# io-ol.net
KiCad netlist of a schematic drawn in EAGLE
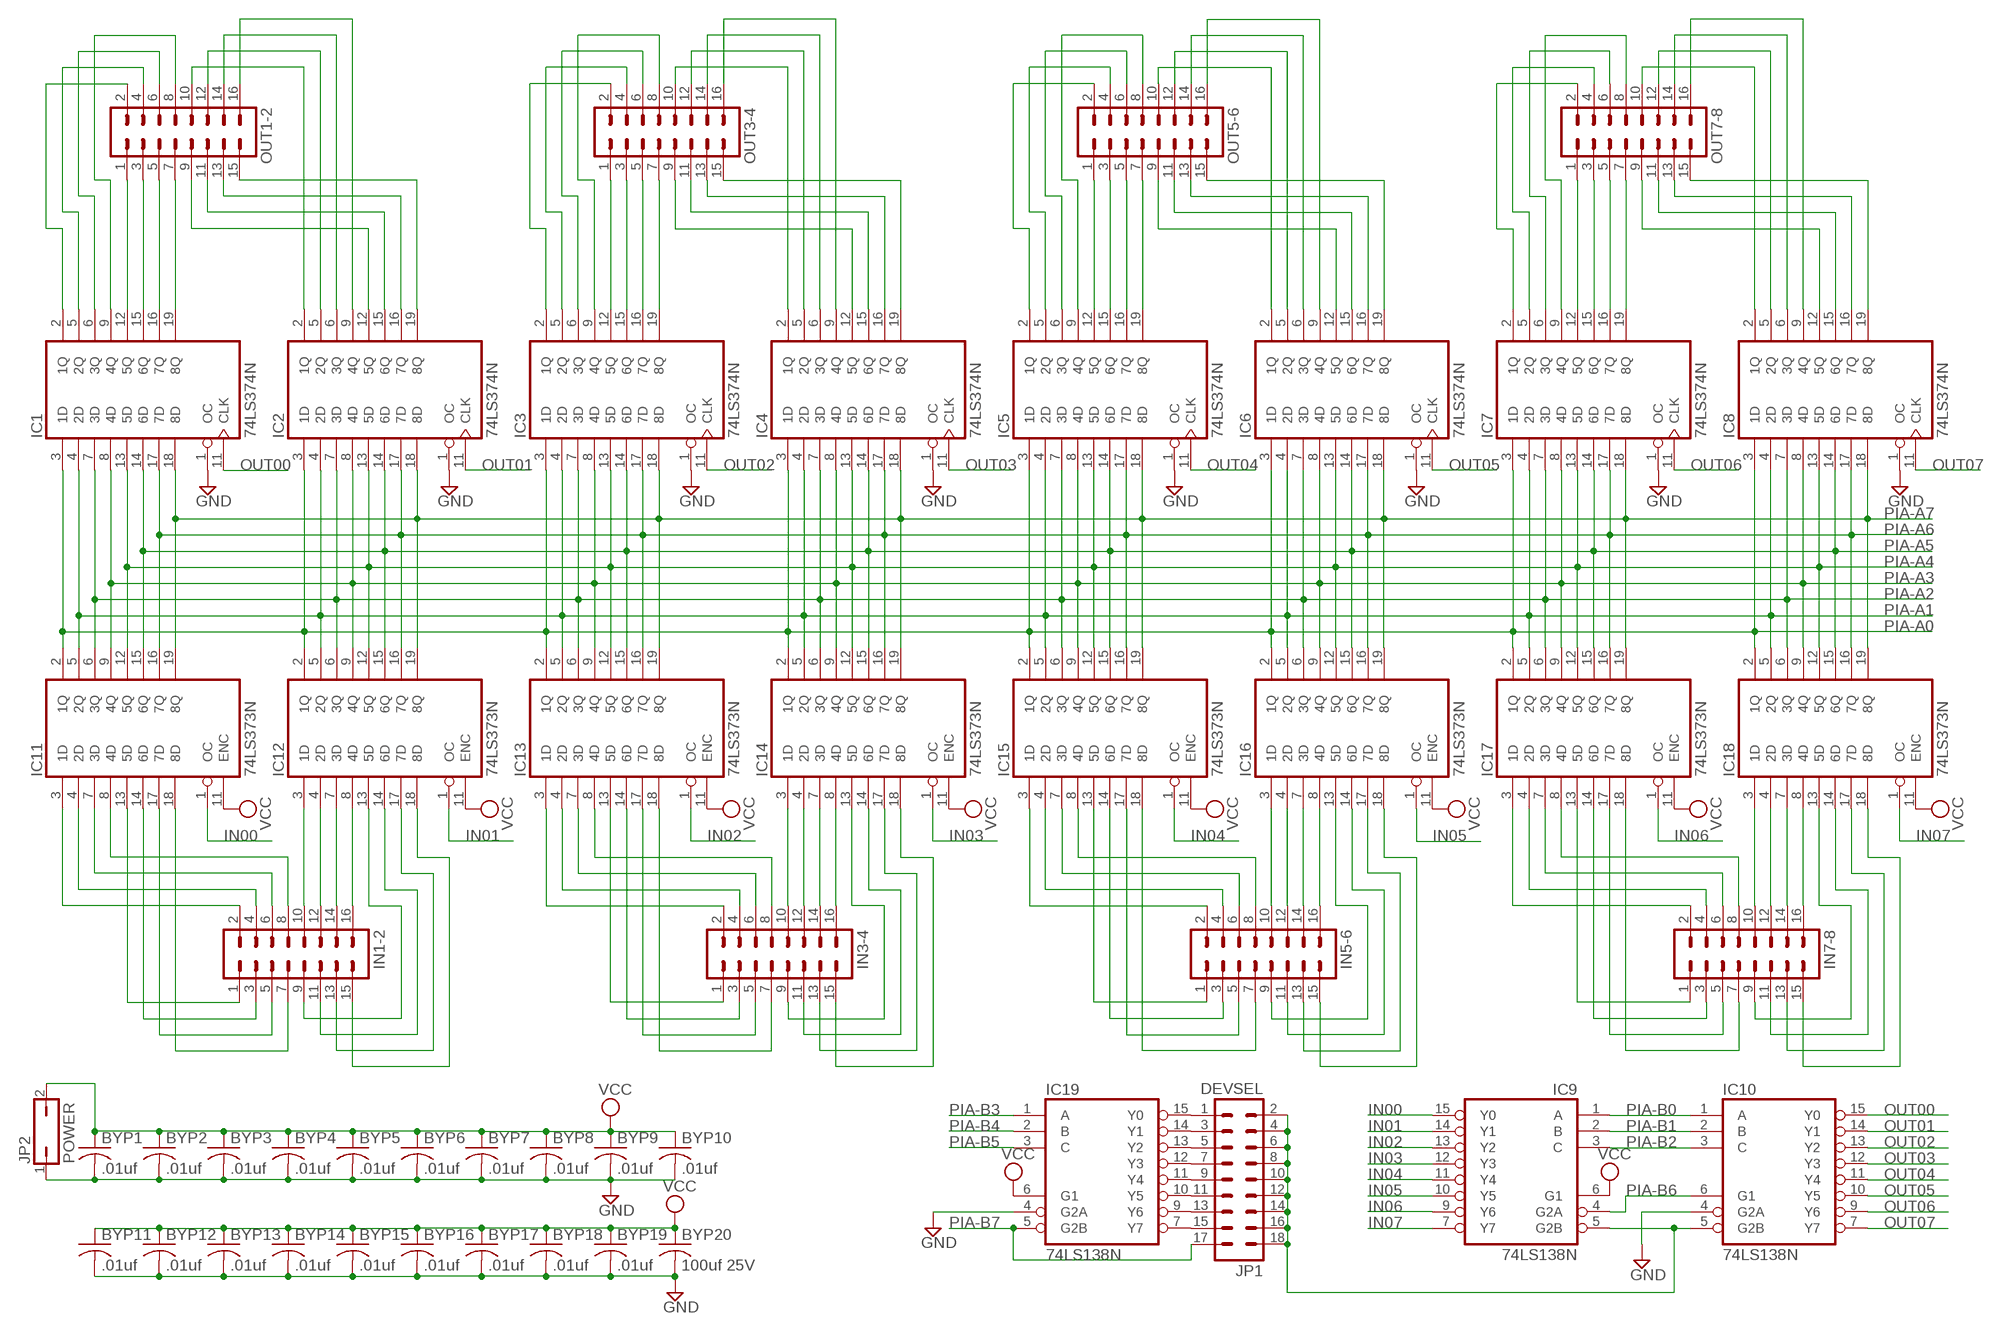
[diagram p0: schematic, sheet 1]
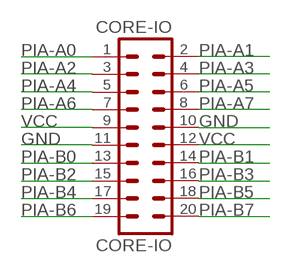
[diagram p1: schematic, sheet 2]

(export (version "E")
  (design (tool "Eeschema 10.0.6"))
  (components
    (comp (ref "BYP1")
      (value ".01uf")
      (footprint "eagle-import:C050-025X075")
      (libsource (lib "eagle-import") (part "C-US050-025X075"))
    )
    (comp (ref "BYP2")
      (value ".01uf")
      (footprint "eagle-import:C050-025X075")
      (libsource (lib "eagle-import") (part "C-US050-025X075"))
    )
    (comp (ref "BYP3")
      (value ".01uf")
      (footprint "eagle-import:C050-025X075")
      (libsource (lib "eagle-import") (part "C-US050-025X075"))
    )
    (comp (ref "BYP4")
      (value ".01uf")
      (footprint "eagle-import:C050-025X075")
      (libsource (lib "eagle-import") (part "C-US050-025X075"))
    )
    (comp (ref "BYP5")
      (value ".01uf")
      (footprint "eagle-import:C050-025X075")
      (libsource (lib "eagle-import") (part "C-US050-025X075"))
    )
    (comp (ref "BYP6")
      (value ".01uf")
      (footprint "eagle-import:C050-025X075")
      (libsource (lib "eagle-import") (part "C-US050-025X075"))
    )
    (comp (ref "BYP7")
      (value ".01uf")
      (footprint "eagle-import:C050-025X075")
      (libsource (lib "eagle-import") (part "C-US050-025X075"))
    )
    (comp (ref "BYP8")
      (value ".01uf")
      (footprint "eagle-import:C050-025X075")
      (libsource (lib "eagle-import") (part "C-US050-025X075"))
    )
    (comp (ref "BYP9")
      (value ".01uf")
      (footprint "eagle-import:C050-025X075")
      (libsource (lib "eagle-import") (part "C-US050-025X075"))
    )
    (comp (ref "BYP10")
      (value ".01uf")
      (footprint "eagle-import:C050-025X075")
      (libsource (lib "eagle-import") (part "C-US050-025X075"))
    )
    (comp (ref "BYP11")
      (value ".01uf")
      (footprint "eagle-import:C050-025X075")
      (libsource (lib "eagle-import") (part "C-US050-025X075"))
    )
    (comp (ref "BYP12")
      (value ".01uf")
      (footprint "eagle-import:C050-025X075")
      (libsource (lib "eagle-import") (part "C-US050-025X075"))
    )
    (comp (ref "BYP13")
      (value ".01uf")
      (footprint "eagle-import:C050-025X075")
      (libsource (lib "eagle-import") (part "C-US050-025X075"))
    )
    (comp (ref "BYP14")
      (value ".01uf")
      (footprint "eagle-import:C050-025X075")
      (libsource (lib "eagle-import") (part "C-US050-025X075"))
    )
    (comp (ref "BYP15")
      (value ".01uf")
      (footprint "eagle-import:C050-025X075")
      (libsource (lib "eagle-import") (part "C-US050-025X075"))
    )
    (comp (ref "BYP16")
      (value ".01uf")
      (footprint "eagle-import:C050-025X075")
      (libsource (lib "eagle-import") (part "C-US050-025X075"))
    )
    (comp (ref "BYP17")
      (value ".01uf")
      (footprint "eagle-import:C050-025X075")
      (libsource (lib "eagle-import") (part "C-US050-025X075"))
    )
    (comp (ref "BYP18")
      (value ".01uf")
      (footprint "eagle-import:C050-025X075")
      (libsource (lib "eagle-import") (part "C-US050-025X075"))
    )
    (comp (ref "BYP19")
      (value ".01uf")
      (footprint "eagle-import:C050-025X075")
      (libsource (lib "eagle-import") (part "C-US050-025X075"))
    )
    (comp (ref "BYP20")
      (value "100uf 25V")
      (footprint "eagle-import:C150-064X183")
      (libsource (lib "eagle-import") (part "C-US150-064X183"))
    )
    (comp (ref "IC1")
      (value "74LS374N")
      (footprint "eagle-import:DIL20")
      (libsource (lib "eagle-import") (part "74374NLS"))
    )
    (comp (ref "IC2")
      (value "74LS374N")
      (footprint "eagle-import:DIL20")
      (libsource (lib "eagle-import") (part "74374NLS"))
    )
    (comp (ref "IC3")
      (value "74LS374N")
      (footprint "eagle-import:DIL20")
      (libsource (lib "eagle-import") (part "74374NLS"))
    )
    (comp (ref "IC4")
      (value "74LS374N")
      (footprint "eagle-import:DIL20")
      (libsource (lib "eagle-import") (part "74374NLS"))
    )
    (comp (ref "IC5")
      (value "74LS374N")
      (footprint "eagle-import:DIL20")
      (libsource (lib "eagle-import") (part "74374NLS"))
    )
    (comp (ref "IC6")
      (value "74LS374N")
      (footprint "eagle-import:DIL20")
      (libsource (lib "eagle-import") (part "74374NLS"))
    )
    (comp (ref "IC7")
      (value "74LS374N")
      (footprint "eagle-import:DIL20")
      (libsource (lib "eagle-import") (part "74374NLS"))
    )
    (comp (ref "IC8")
      (value "74LS374N")
      (footprint "eagle-import:DIL20")
      (libsource (lib "eagle-import") (part "74374NLS"))
    )
    (comp (ref "IC9")
      (value "74LS138N")
      (footprint "eagle-import:DIL16")
      (libsource (lib "eagle-import") (part "74138NLS"))
    )
    (comp (ref "IC10")
      (value "74LS138N")
      (footprint "eagle-import:DIL16")
      (libsource (lib "eagle-import") (part "74138NLS"))
    )
    (comp (ref "IC11")
      (value "74LS373N")
      (footprint "eagle-import:DIL20")
      (libsource (lib "eagle-import") (part "74373NLS"))
    )
    (comp (ref "IC12")
      (value "74LS373N")
      (footprint "eagle-import:DIL20")
      (libsource (lib "eagle-import") (part "74373NLS"))
    )
    (comp (ref "IC13")
      (value "74LS373N")
      (footprint "eagle-import:DIL20")
      (libsource (lib "eagle-import") (part "74373NLS"))
    )
    (comp (ref "IC14")
      (value "74LS373N")
      (footprint "eagle-import:DIL20")
      (libsource (lib "eagle-import") (part "74373NLS"))
    )
    (comp (ref "IC15")
      (value "74LS373N")
      (footprint "eagle-import:DIL20")
      (libsource (lib "eagle-import") (part "74373NLS"))
    )
    (comp (ref "IC16")
      (value "74LS373N")
      (footprint "eagle-import:DIL20")
      (libsource (lib "eagle-import") (part "74373NLS"))
    )
    (comp (ref "IC17")
      (value "74LS373N")
      (footprint "eagle-import:DIL20")
      (libsource (lib "eagle-import") (part "74373NLS"))
    )
    (comp (ref "IC18")
      (value "74LS373N")
      (footprint "eagle-import:DIL20")
      (libsource (lib "eagle-import") (part "74373NLS"))
    )
    (comp (ref "IC19")
      (value "74LS138N")
      (footprint "eagle-import:DIL16")
      (libsource (lib "eagle-import") (part "74138NLS"))
    )
    (comp (ref "IN1-2")
      (value "MA08-2")
      (footprint "eagle-import:MA08-2")
      (libsource (lib "eagle-import") (part "MA08-2"))
    )
    (comp (ref "IN3-4")
      (value "MA08-2")
      (footprint "eagle-import:MA08-2")
      (libsource (lib "eagle-import") (part "MA08-2"))
    )
    (comp (ref "IN5-6")
      (value "MA08-2")
      (footprint "eagle-import:MA08-2")
      (libsource (lib "eagle-import") (part "MA08-2"))
    )
    (comp (ref "IN7-8")
      (value "MA08-2")
      (footprint "eagle-import:MA08-2")
      (libsource (lib "eagle-import") (part "MA08-2"))
    )
    (comp (ref "JP1")
      (value "DEVSEL")
      (footprint "eagle-import:MA09-2")
      (libsource (lib "eagle-import") (part "MA09-2"))
    )
    (comp (ref "JP2")
      (value "POWER")
      (footprint "eagle-import:JP1")
      (libsource (lib "eagle-import") (part "JP1Q"))
    )
    (comp (ref "OUT1-2")
      (value "MA08-2")
      (footprint "eagle-import:MA08-2")
      (libsource (lib "eagle-import") (part "MA08-2"))
    )
    (comp (ref "OUT3-4")
      (value "MA08-2")
      (footprint "eagle-import:MA08-2")
      (libsource (lib "eagle-import") (part "MA08-2"))
    )
    (comp (ref "OUT5-6")
      (value "MA08-2")
      (footprint "eagle-import:MA08-2")
      (libsource (lib "eagle-import") (part "MA08-2"))
    )
    (comp (ref "OUT7-8")
      (value "MA08-2")
      (footprint "eagle-import:MA08-2")
      (libsource (lib "eagle-import") (part "MA08-2"))
    )
    (comp (ref "CORE-IO")
      (value "CORE-IO")
      (footprint "eagle-import:MA10-2")
      (libsource (lib "eagle-import") (part "MA10-2"))
    )
  )
  (nets
    (net (code "1") (name "GND") (class "Default")
      (node (ref "BYP1") (pin "2") (pinfunction "2_2") (pintype "passive"))
      (node (ref "BYP10") (pin "2") (pinfunction "2_2") (pintype "passive"))
      (node (ref "BYP11") (pin "2") (pinfunction "2_2") (pintype "passive"))
      (node (ref "BYP12") (pin "2") (pinfunction "2_2") (pintype "passive"))
      (node (ref "BYP13") (pin "2") (pinfunction "2_2") (pintype "passive"))
      (node (ref "BYP14") (pin "2") (pinfunction "2_2") (pintype "passive"))
      (node (ref "BYP15") (pin "2") (pinfunction "2_2") (pintype "passive"))
      (node (ref "BYP16") (pin "2") (pinfunction "2_2") (pintype "passive"))
      (node (ref "BYP17") (pin "2") (pinfunction "2_2") (pintype "passive"))
      (node (ref "BYP18") (pin "2") (pinfunction "2_2") (pintype "passive"))
      (node (ref "BYP19") (pin "2") (pinfunction "2_2") (pintype "passive"))
      (node (ref "BYP2") (pin "2") (pinfunction "2_2") (pintype "passive"))
      (node (ref "BYP20") (pin "2") (pinfunction "2_2") (pintype "passive"))
      (node (ref "BYP3") (pin "2") (pinfunction "2_2") (pintype "passive"))
      (node (ref "BYP4") (pin "2") (pinfunction "2_2") (pintype "passive"))
      (node (ref "BYP5") (pin "2") (pinfunction "2_2") (pintype "passive"))
      (node (ref "BYP6") (pin "2") (pinfunction "2_2") (pintype "passive"))
      (node (ref "BYP7") (pin "2") (pinfunction "2_2") (pintype "passive"))
      (node (ref "BYP8") (pin "2") (pinfunction "2_2") (pintype "passive"))
      (node (ref "BYP9") (pin "2") (pinfunction "2_2") (pintype "passive"))
      (node (ref "CORE-IO") (pin "10") (pinfunction "10_10") (pintype "passive"))
      (node (ref "CORE-IO") (pin "11") (pinfunction "11_11") (pintype "passive"))
      (node (ref "IC1") (pin "1") (pinfunction "OC_1") (pintype "input"))
      (node (ref "IC10") (pin "4") (pinfunction "G2A_4") (pintype "input"))
      (node (ref "IC19") (pin "4") (pinfunction "G2A_4") (pintype "input"))
      (node (ref "IC2") (pin "1") (pinfunction "OC_1") (pintype "input"))
      (node (ref "IC3") (pin "1") (pinfunction "OC_1") (pintype "input"))
      (node (ref "IC4") (pin "1") (pinfunction "OC_1") (pintype "input"))
      (node (ref "IC5") (pin "1") (pinfunction "OC_1") (pintype "input"))
      (node (ref "IC6") (pin "1") (pinfunction "OC_1") (pintype "input"))
      (node (ref "IC7") (pin "1") (pinfunction "OC_1") (pintype "input"))
      (node (ref "IC8") (pin "1") (pinfunction "OC_1") (pintype "input"))
      (node (ref "JP2") (pin "1") (pinfunction "1_1") (pintype "passive"))
    )
    (net (code "2") (name "IN00") (class "Default")
      (node (ref "IC11") (pin "1") (pinfunction "OC_1") (pintype "input"))
      (node (ref "IC9") (pin "15") (pinfunction "Y0_15") (pintype "output"))
    )
    (net (code "3") (name "IN01") (class "Default")
      (node (ref "IC12") (pin "1") (pinfunction "OC_1") (pintype "input"))
      (node (ref "IC9") (pin "14") (pinfunction "Y1_14") (pintype "output"))
    )
    (net (code "4") (name "IN02") (class "Default")
      (node (ref "IC13") (pin "1") (pinfunction "OC_1") (pintype "input"))
      (node (ref "IC9") (pin "13") (pinfunction "Y2_13") (pintype "output"))
    )
    (net (code "5") (name "IN03") (class "Default")
      (node (ref "IC14") (pin "1") (pinfunction "OC_1") (pintype "input"))
      (node (ref "IC9") (pin "12") (pinfunction "Y3_12") (pintype "output"))
    )
    (net (code "6") (name "IN04") (class "Default")
      (node (ref "IC15") (pin "1") (pinfunction "OC_1") (pintype "input"))
      (node (ref "IC9") (pin "11") (pinfunction "Y4_11") (pintype "output"))
    )
    (net (code "7") (name "IN05") (class "Default")
      (node (ref "IC16") (pin "1") (pinfunction "OC_1") (pintype "input"))
      (node (ref "IC9") (pin "10") (pinfunction "Y5_10") (pintype "output"))
    )
    (net (code "8") (name "IN06") (class "Default")
      (node (ref "IC17") (pin "1") (pinfunction "OC_1") (pintype "input"))
      (node (ref "IC9") (pin "9") (pinfunction "Y6_9") (pintype "output"))
    )
    (net (code "9") (name "IN07") (class "Default")
      (node (ref "IC18") (pin "1") (pinfunction "OC_1") (pintype "input"))
      (node (ref "IC9") (pin "7") (pinfunction "Y7_7") (pintype "output"))
    )
    (net (code "10") (name "Net-(IC1A-1Q)") (class "Default")
      (node (ref "IC1") (pin "2") (pinfunction "1Q_2") (pintype "tri_state"))
      (node (ref "OUT1-2") (pin "2") (pinfunction "2_2") (pintype "passive"))
    )
    (net (code "11") (name "Net-(IC1A-2Q)") (class "Default")
      (node (ref "IC1") (pin "5") (pinfunction "2Q_5") (pintype "tri_state"))
      (node (ref "OUT1-2") (pin "4") (pinfunction "4_4") (pintype "passive"))
    )
    (net (code "12") (name "Net-(IC1A-3Q)") (class "Default")
      (node (ref "IC1") (pin "6") (pinfunction "3Q_6") (pintype "tri_state"))
      (node (ref "OUT1-2") (pin "6") (pinfunction "6_6") (pintype "passive"))
    )
    (net (code "13") (name "Net-(IC1A-4Q)") (class "Default")
      (node (ref "IC1") (pin "9") (pinfunction "4Q_9") (pintype "tri_state"))
      (node (ref "OUT1-2") (pin "8") (pinfunction "8_8") (pintype "passive"))
    )
    (net (code "14") (name "Net-(IC1A-5Q)") (class "Default")
      (node (ref "IC1") (pin "12") (pinfunction "5Q_12") (pintype "tri_state"))
      (node (ref "OUT1-2") (pin "1") (pinfunction "1_1") (pintype "passive"))
    )
    (net (code "15") (name "Net-(IC1A-6Q)") (class "Default")
      (node (ref "IC1") (pin "15") (pinfunction "6Q_15") (pintype "tri_state"))
      (node (ref "OUT1-2") (pin "3") (pinfunction "3_3") (pintype "passive"))
    )
    (net (code "16") (name "Net-(IC1A-7Q)") (class "Default")
      (node (ref "IC1") (pin "16") (pinfunction "7Q_16") (pintype "tri_state"))
      (node (ref "OUT1-2") (pin "5") (pinfunction "5_5") (pintype "passive"))
    )
    (net (code "17") (name "Net-(IC1A-8Q)") (class "Default")
      (node (ref "IC1") (pin "19") (pinfunction "8Q_19") (pintype "tri_state"))
      (node (ref "OUT1-2") (pin "7") (pinfunction "7_7") (pintype "passive"))
    )
    (net (code "18") (name "Net-(IC2A-1Q)") (class "Default")
      (node (ref "IC2") (pin "2") (pinfunction "1Q_2") (pintype "tri_state"))
      (node (ref "OUT1-2") (pin "10") (pinfunction "10_10") (pintype "passive"))
    )
    (net (code "19") (name "Net-(IC2A-2Q)") (class "Default")
      (node (ref "IC2") (pin "5") (pinfunction "2Q_5") (pintype "tri_state"))
      (node (ref "OUT1-2") (pin "12") (pinfunction "12_12") (pintype "passive"))
    )
    (net (code "20") (name "Net-(IC2A-3Q)") (class "Default")
      (node (ref "IC2") (pin "6") (pinfunction "3Q_6") (pintype "tri_state"))
      (node (ref "OUT1-2") (pin "14") (pinfunction "14_14") (pintype "passive"))
    )
    (net (code "21") (name "Net-(IC2A-4Q)") (class "Default")
      (node (ref "IC2") (pin "9") (pinfunction "4Q_9") (pintype "tri_state"))
      (node (ref "OUT1-2") (pin "16") (pinfunction "16_16") (pintype "passive"))
    )
    (net (code "22") (name "Net-(IC2A-5Q)") (class "Default")
      (node (ref "IC2") (pin "12") (pinfunction "5Q_12") (pintype "tri_state"))
      (node (ref "OUT1-2") (pin "9") (pinfunction "9_9") (pintype "passive"))
    )
    (net (code "23") (name "Net-(IC2A-6Q)") (class "Default")
      (node (ref "IC2") (pin "15") (pinfunction "6Q_15") (pintype "tri_state"))
      (node (ref "OUT1-2") (pin "11") (pinfunction "11_11") (pintype "passive"))
    )
    (net (code "24") (name "Net-(IC2A-7Q)") (class "Default")
      (node (ref "IC2") (pin "16") (pinfunction "7Q_16") (pintype "tri_state"))
      (node (ref "OUT1-2") (pin "13") (pinfunction "13_13") (pintype "passive"))
    )
    (net (code "25") (name "Net-(IC2A-8Q)") (class "Default")
      (node (ref "IC2") (pin "19") (pinfunction "8Q_19") (pintype "tri_state"))
      (node (ref "OUT1-2") (pin "15") (pinfunction "15_15") (pintype "passive"))
    )
    (net (code "26") (name "Net-(IC3A-1Q)") (class "Default")
      (node (ref "IC3") (pin "2") (pinfunction "1Q_2") (pintype "tri_state"))
      (node (ref "OUT3-4") (pin "2") (pinfunction "2_2") (pintype "passive"))
    )
    (net (code "27") (name "Net-(IC3A-2Q)") (class "Default")
      (node (ref "IC3") (pin "5") (pinfunction "2Q_5") (pintype "tri_state"))
      (node (ref "OUT3-4") (pin "4") (pinfunction "4_4") (pintype "passive"))
    )
    (net (code "28") (name "Net-(IC3A-3Q)") (class "Default")
      (node (ref "IC3") (pin "6") (pinfunction "3Q_6") (pintype "tri_state"))
      (node (ref "OUT3-4") (pin "6") (pinfunction "6_6") (pintype "passive"))
    )
    (net (code "29") (name "Net-(IC3A-4Q)") (class "Default")
      (node (ref "IC3") (pin "9") (pinfunction "4Q_9") (pintype "tri_state"))
      (node (ref "OUT3-4") (pin "8") (pinfunction "8_8") (pintype "passive"))
    )
    (net (code "30") (name "Net-(IC3A-5Q)") (class "Default")
      (node (ref "IC3") (pin "12") (pinfunction "5Q_12") (pintype "tri_state"))
      (node (ref "OUT3-4") (pin "1") (pinfunction "1_1") (pintype "passive"))
    )
    (net (code "31") (name "Net-(IC3A-6Q)") (class "Default")
      (node (ref "IC3") (pin "15") (pinfunction "6Q_15") (pintype "tri_state"))
      (node (ref "OUT3-4") (pin "3") (pinfunction "3_3") (pintype "passive"))
    )
    (net (code "32") (name "Net-(IC3A-7Q)") (class "Default")
      (node (ref "IC3") (pin "16") (pinfunction "7Q_16") (pintype "tri_state"))
      (node (ref "OUT3-4") (pin "5") (pinfunction "5_5") (pintype "passive"))
    )
    (net (code "33") (name "Net-(IC3A-8Q)") (class "Default")
      (node (ref "IC3") (pin "19") (pinfunction "8Q_19") (pintype "tri_state"))
      (node (ref "OUT3-4") (pin "7") (pinfunction "7_7") (pintype "passive"))
    )
    (net (code "34") (name "Net-(IC4A-1Q)") (class "Default")
      (node (ref "IC4") (pin "2") (pinfunction "1Q_2") (pintype "tri_state"))
      (node (ref "OUT3-4") (pin "10") (pinfunction "10_10") (pintype "passive"))
    )
    (net (code "35") (name "Net-(IC4A-2Q)") (class "Default")
      (node (ref "IC4") (pin "5") (pinfunction "2Q_5") (pintype "tri_state"))
      (node (ref "OUT3-4") (pin "12") (pinfunction "12_12") (pintype "passive"))
    )
    (net (code "36") (name "Net-(IC4A-3Q)") (class "Default")
      (node (ref "IC4") (pin "6") (pinfunction "3Q_6") (pintype "tri_state"))
      (node (ref "OUT3-4") (pin "14") (pinfunction "14_14") (pintype "passive"))
    )
    (net (code "37") (name "Net-(IC4A-4Q)") (class "Default")
      (node (ref "IC4") (pin "9") (pinfunction "4Q_9") (pintype "tri_state"))
      (node (ref "OUT3-4") (pin "16") (pinfunction "16_16") (pintype "passive"))
    )
    (net (code "38") (name "Net-(IC4A-5Q)") (class "Default")
      (node (ref "IC4") (pin "12") (pinfunction "5Q_12") (pintype "tri_state"))
      (node (ref "OUT3-4") (pin "9") (pinfunction "9_9") (pintype "passive"))
    )
    (net (code "39") (name "Net-(IC4A-6Q)") (class "Default")
      (node (ref "IC4") (pin "15") (pinfunction "6Q_15") (pintype "tri_state"))
      (node (ref "OUT3-4") (pin "11") (pinfunction "11_11") (pintype "passive"))
    )
    (net (code "40") (name "Net-(IC4A-7Q)") (class "Default")
      (node (ref "IC4") (pin "16") (pinfunction "7Q_16") (pintype "tri_state"))
      (node (ref "OUT3-4") (pin "13") (pinfunction "13_13") (pintype "passive"))
    )
    (net (code "41") (name "Net-(IC4A-8Q)") (class "Default")
      (node (ref "IC4") (pin "19") (pinfunction "8Q_19") (pintype "tri_state"))
      (node (ref "OUT3-4") (pin "15") (pinfunction "15_15") (pintype "passive"))
    )
    (net (code "42") (name "Net-(IC5A-1Q)") (class "Default")
      (node (ref "IC5") (pin "2") (pinfunction "1Q_2") (pintype "tri_state"))
      (node (ref "OUT5-6") (pin "2") (pinfunction "2_2") (pintype "passive"))
    )
    (net (code "43") (name "Net-(IC5A-2Q)") (class "Default")
      (node (ref "IC5") (pin "5") (pinfunction "2Q_5") (pintype "tri_state"))
      (node (ref "OUT5-6") (pin "4") (pinfunction "4_4") (pintype "passive"))
    )
    (net (code "44") (name "Net-(IC5A-3Q)") (class "Default")
      (node (ref "IC5") (pin "6") (pinfunction "3Q_6") (pintype "tri_state"))
      (node (ref "OUT5-6") (pin "6") (pinfunction "6_6") (pintype "passive"))
    )
    (net (code "45") (name "Net-(IC5A-4Q)") (class "Default")
      (node (ref "IC5") (pin "9") (pinfunction "4Q_9") (pintype "tri_state"))
      (node (ref "OUT5-6") (pin "8") (pinfunction "8_8") (pintype "passive"))
    )
    (net (code "46") (name "Net-(IC5A-5Q)") (class "Default")
      (node (ref "IC5") (pin "12") (pinfunction "5Q_12") (pintype "tri_state"))
      (node (ref "OUT5-6") (pin "1") (pinfunction "1_1") (pintype "passive"))
    )
    (net (code "47") (name "Net-(IC5A-6Q)") (class "Default")
      (node (ref "IC5") (pin "15") (pinfunction "6Q_15") (pintype "tri_state"))
      (node (ref "OUT5-6") (pin "3") (pinfunction "3_3") (pintype "passive"))
    )
    (net (code "48") (name "Net-(IC5A-7Q)") (class "Default")
      (node (ref "IC5") (pin "16") (pinfunction "7Q_16") (pintype "tri_state"))
      (node (ref "OUT5-6") (pin "5") (pinfunction "5_5") (pintype "passive"))
    )
    (net (code "49") (name "Net-(IC5A-8Q)") (class "Default")
      (node (ref "IC5") (pin "19") (pinfunction "8Q_19") (pintype "tri_state"))
      (node (ref "OUT5-6") (pin "7") (pinfunction "7_7") (pintype "passive"))
    )
    (net (code "50") (name "Net-(IC6A-1Q)") (class "Default")
      (node (ref "IC6") (pin "2") (pinfunction "1Q_2") (pintype "tri_state"))
      (node (ref "OUT5-6") (pin "10") (pinfunction "10_10") (pintype "passive"))
    )
    (net (code "51") (name "Net-(IC6A-2Q)") (class "Default")
      (node (ref "IC6") (pin "5") (pinfunction "2Q_5") (pintype "tri_state"))
      (node (ref "OUT5-6") (pin "12") (pinfunction "12_12") (pintype "passive"))
    )
    (net (code "52") (name "Net-(IC6A-3Q)") (class "Default")
      (node (ref "IC6") (pin "6") (pinfunction "3Q_6") (pintype "tri_state"))
      (node (ref "OUT5-6") (pin "14") (pinfunction "14_14") (pintype "passive"))
    )
    (net (code "53") (name "Net-(IC6A-4Q)") (class "Default")
      (node (ref "IC6") (pin "9") (pinfunction "4Q_9") (pintype "tri_state"))
      (node (ref "OUT5-6") (pin "16") (pinfunction "16_16") (pintype "passive"))
    )
    (net (code "54") (name "Net-(IC6A-5Q)") (class "Default")
      (node (ref "IC6") (pin "12") (pinfunction "5Q_12") (pintype "tri_state"))
      (node (ref "OUT5-6") (pin "9") (pinfunction "9_9") (pintype "passive"))
    )
    (net (code "55") (name "Net-(IC6A-6Q)") (class "Default")
      (node (ref "IC6") (pin "15") (pinfunction "6Q_15") (pintype "tri_state"))
      (node (ref "OUT5-6") (pin "11") (pinfunction "11_11") (pintype "passive"))
    )
    (net (code "56") (name "Net-(IC6A-7Q)") (class "Default")
      (node (ref "IC6") (pin "16") (pinfunction "7Q_16") (pintype "tri_state"))
      (node (ref "OUT5-6") (pin "13") (pinfunction "13_13") (pintype "passive"))
    )
    (net (code "57") (name "Net-(IC6A-8Q)") (class "Default")
      (node (ref "IC6") (pin "19") (pinfunction "8Q_19") (pintype "tri_state"))
      (node (ref "OUT5-6") (pin "15") (pinfunction "15_15") (pintype "passive"))
    )
    (net (code "58") (name "Net-(IC7A-1Q)") (class "Default")
      (node (ref "IC7") (pin "2") (pinfunction "1Q_2") (pintype "tri_state"))
      (node (ref "OUT7-8") (pin "2") (pinfunction "2_2") (pintype "passive"))
    )
    (net (code "59") (name "Net-(IC7A-2Q)") (class "Default")
      (node (ref "IC7") (pin "5") (pinfunction "2Q_5") (pintype "tri_state"))
      (node (ref "OUT7-8") (pin "4") (pinfunction "4_4") (pintype "passive"))
    )
    (net (code "60") (name "Net-(IC7A-3Q)") (class "Default")
      (node (ref "IC7") (pin "6") (pinfunction "3Q_6") (pintype "tri_state"))
      (node (ref "OUT7-8") (pin "6") (pinfunction "6_6") (pintype "passive"))
    )
    (net (code "61") (name "Net-(IC7A-4Q)") (class "Default")
      (node (ref "IC7") (pin "9") (pinfunction "4Q_9") (pintype "tri_state"))
      (node (ref "OUT7-8") (pin "8") (pinfunction "8_8") (pintype "passive"))
    )
    (net (code "62") (name "Net-(IC7A-5Q)") (class "Default")
      (node (ref "IC7") (pin "12") (pinfunction "5Q_12") (pintype "tri_state"))
      (node (ref "OUT7-8") (pin "1") (pinfunction "1_1") (pintype "passive"))
    )
    (net (code "63") (name "Net-(IC7A-6Q)") (class "Default")
      (node (ref "IC7") (pin "15") (pinfunction "6Q_15") (pintype "tri_state"))
      (node (ref "OUT7-8") (pin "3") (pinfunction "3_3") (pintype "passive"))
    )
    (net (code "64") (name "Net-(IC7A-7Q)") (class "Default")
      (node (ref "IC7") (pin "16") (pinfunction "7Q_16") (pintype "tri_state"))
      (node (ref "OUT7-8") (pin "5") (pinfunction "5_5") (pintype "passive"))
    )
    (net (code "65") (name "Net-(IC7A-8Q)") (class "Default")
      (node (ref "IC7") (pin "19") (pinfunction "8Q_19") (pintype "tri_state"))
      (node (ref "OUT7-8") (pin "7") (pinfunction "7_7") (pintype "passive"))
    )
    (net (code "66") (name "Net-(IC8A-1Q)") (class "Default")
      (node (ref "IC8") (pin "2") (pinfunction "1Q_2") (pintype "tri_state"))
      (node (ref "OUT7-8") (pin "10") (pinfunction "10_10") (pintype "passive"))
    )
    (net (code "67") (name "Net-(IC8A-2Q)") (class "Default")
      (node (ref "IC8") (pin "5") (pinfunction "2Q_5") (pintype "tri_state"))
      (node (ref "OUT7-8") (pin "12") (pinfunction "12_12") (pintype "passive"))
    )
    (net (code "68") (name "Net-(IC8A-3Q)") (class "Default")
      (node (ref "IC8") (pin "6") (pinfunction "3Q_6") (pintype "tri_state"))
      (node (ref "OUT7-8") (pin "14") (pinfunction "14_14") (pintype "passive"))
    )
    (net (code "69") (name "Net-(IC8A-4Q)") (class "Default")
      (node (ref "IC8") (pin "9") (pinfunction "4Q_9") (pintype "tri_state"))
      (node (ref "OUT7-8") (pin "16") (pinfunction "16_16") (pintype "passive"))
    )
    (net (code "70") (name "Net-(IC8A-5Q)") (class "Default")
      (node (ref "IC8") (pin "12") (pinfunction "5Q_12") (pintype "tri_state"))
      (node (ref "OUT7-8") (pin "9") (pinfunction "9_9") (pintype "passive"))
    )
    (net (code "71") (name "Net-(IC8A-6Q)") (class "Default")
      (node (ref "IC8") (pin "15") (pinfunction "6Q_15") (pintype "tri_state"))
      (node (ref "OUT7-8") (pin "11") (pinfunction "11_11") (pintype "passive"))
    )
    (net (code "72") (name "Net-(IC8A-7Q)") (class "Default")
      (node (ref "IC8") (pin "16") (pinfunction "7Q_16") (pintype "tri_state"))
      (node (ref "OUT7-8") (pin "13") (pinfunction "13_13") (pintype "passive"))
    )
    (net (code "73") (name "Net-(IC8A-8Q)") (class "Default")
      (node (ref "IC8") (pin "19") (pinfunction "8Q_19") (pintype "tri_state"))
      (node (ref "OUT7-8") (pin "15") (pinfunction "15_15") (pintype "passive"))
    )
    (net (code "74") (name "Net-(IC10A-G2B)") (class "Default")
      (node (ref "IC10") (pin "5") (pinfunction "G2B_5") (pintype "input"))
      (node (ref "IC9") (pin "5") (pinfunction "G2B_5") (pintype "input"))
      (node (ref "JP1") (pin "10") (pinfunction "10_10") (pintype "passive"))
      (node (ref "JP1") (pin "12") (pinfunction "12_12") (pintype "passive"))
      (node (ref "JP1") (pin "14") (pinfunction "14_14") (pintype "passive"))
      (node (ref "JP1") (pin "16") (pinfunction "16_16") (pintype "passive"))
      (node (ref "JP1") (pin "18") (pinfunction "18_18") (pintype "passive"))
      (node (ref "JP1") (pin "2") (pinfunction "2_2") (pintype "passive"))
      (node (ref "JP1") (pin "4") (pinfunction "4_4") (pintype "passive"))
      (node (ref "JP1") (pin "6") (pinfunction "6_6") (pintype "passive"))
      (node (ref "JP1") (pin "8") (pinfunction "8_8") (pintype "passive"))
    )
    (net (code "75") (name "Net-(IC11A-1D)") (class "Default")
      (node (ref "IC11") (pin "3") (pinfunction "1D_3") (pintype "input"))
      (node (ref "IN1-2") (pin "2") (pinfunction "2_2") (pintype "passive"))
    )
    (net (code "76") (name "Net-(IC11A-2D)") (class "Default")
      (node (ref "IC11") (pin "4") (pinfunction "2D_4") (pintype "input"))
      (node (ref "IN1-2") (pin "4") (pinfunction "4_4") (pintype "passive"))
    )
    (net (code "77") (name "Net-(IC11A-3D)") (class "Default")
      (node (ref "IC11") (pin "7") (pinfunction "3D_7") (pintype "input"))
      (node (ref "IN1-2") (pin "6") (pinfunction "6_6") (pintype "passive"))
    )
    (net (code "78") (name "Net-(IC11A-4D)") (class "Default")
      (node (ref "IC11") (pin "8") (pinfunction "4D_8") (pintype "input"))
      (node (ref "IN1-2") (pin "8") (pinfunction "8_8") (pintype "passive"))
    )
    (net (code "79") (name "Net-(IC11A-5D)") (class "Default")
      (node (ref "IC11") (pin "13") (pinfunction "5D_13") (pintype "input"))
      (node (ref "IN1-2") (pin "1") (pinfunction "1_1") (pintype "passive"))
    )
    (net (code "80") (name "Net-(IC11A-6D)") (class "Default")
      (node (ref "IC11") (pin "14") (pinfunction "6D_14") (pintype "input"))
      (node (ref "IN1-2") (pin "3") (pinfunction "3_3") (pintype "passive"))
    )
    (net (code "81") (name "Net-(IC11A-7D)") (class "Default")
      (node (ref "IC11") (pin "17") (pinfunction "7D_17") (pintype "input"))
      (node (ref "IN1-2") (pin "5") (pinfunction "5_5") (pintype "passive"))
    )
    (net (code "82") (name "Net-(IC11A-8D)") (class "Default")
      (node (ref "IC11") (pin "18") (pinfunction "8D_18") (pintype "input"))
      (node (ref "IN1-2") (pin "7") (pinfunction "7_7") (pintype "passive"))
    )
    (net (code "83") (name "Net-(IC12A-1D)") (class "Default")
      (node (ref "IC12") (pin "3") (pinfunction "1D_3") (pintype "input"))
      (node (ref "IN1-2") (pin "10") (pinfunction "10_10") (pintype "passive"))
    )
    (net (code "84") (name "Net-(IC12A-2D)") (class "Default")
      (node (ref "IC12") (pin "4") (pinfunction "2D_4") (pintype "input"))
      (node (ref "IN1-2") (pin "12") (pinfunction "12_12") (pintype "passive"))
    )
    (net (code "85") (name "Net-(IC12A-3D)") (class "Default")
      (node (ref "IC12") (pin "7") (pinfunction "3D_7") (pintype "input"))
      (node (ref "IN1-2") (pin "14") (pinfunction "14_14") (pintype "passive"))
    )
    (net (code "86") (name "Net-(IC12A-4D)") (class "Default")
      (node (ref "IC12") (pin "8") (pinfunction "4D_8") (pintype "input"))
      (node (ref "IN1-2") (pin "16") (pinfunction "16_16") (pintype "passive"))
    )
    (net (code "87") (name "Net-(IC12A-5D)") (class "Default")
      (node (ref "IC12") (pin "13") (pinfunction "5D_13") (pintype "input"))
      (node (ref "IN1-2") (pin "9") (pinfunction "9_9") (pintype "passive"))
    )
    (net (code "88") (name "Net-(IC12A-6D)") (class "Default")
      (node (ref "IC12") (pin "14") (pinfunction "6D_14") (pintype "input"))
      (node (ref "IN1-2") (pin "11") (pinfunction "11_11") (pintype "passive"))
    )
    (net (code "89") (name "Net-(IC12A-7D)") (class "Default")
      (node (ref "IC12") (pin "17") (pinfunction "7D_17") (pintype "input"))
      (node (ref "IN1-2") (pin "13") (pinfunction "13_13") (pintype "passive"))
    )
    (net (code "90") (name "Net-(IC12A-8D)") (class "Default")
      (node (ref "IC12") (pin "18") (pinfunction "8D_18") (pintype "input"))
      (node (ref "IN1-2") (pin "15") (pinfunction "15_15") (pintype "passive"))
    )
    (net (code "91") (name "Net-(IC13A-1D)") (class "Default")
      (node (ref "IC13") (pin "3") (pinfunction "1D_3") (pintype "input"))
      (node (ref "IN3-4") (pin "2") (pinfunction "2_2") (pintype "passive"))
    )
    (net (code "92") (name "Net-(IC13A-2D)") (class "Default")
      (node (ref "IC13") (pin "4") (pinfunction "2D_4") (pintype "input"))
      (node (ref "IN3-4") (pin "4") (pinfunction "4_4") (pintype "passive"))
    )
    (net (code "93") (name "Net-(IC13A-3D)") (class "Default")
      (node (ref "IC13") (pin "7") (pinfunction "3D_7") (pintype "input"))
      (node (ref "IN3-4") (pin "6") (pinfunction "6_6") (pintype "passive"))
    )
    (net (code "94") (name "Net-(IC13A-4D)") (class "Default")
      (node (ref "IC13") (pin "8") (pinfunction "4D_8") (pintype "input"))
      (node (ref "IN3-4") (pin "8") (pinfunction "8_8") (pintype "passive"))
    )
    (net (code "95") (name "Net-(IC13A-5D)") (class "Default")
      (node (ref "IC13") (pin "13") (pinfunction "5D_13") (pintype "input"))
      (node (ref "IN3-4") (pin "1") (pinfunction "1_1") (pintype "passive"))
    )
    (net (code "96") (name "Net-(IC13A-6D)") (class "Default")
      (node (ref "IC13") (pin "14") (pinfunction "6D_14") (pintype "input"))
      (node (ref "IN3-4") (pin "3") (pinfunction "3_3") (pintype "passive"))
    )
    (net (code "97") (name "Net-(IC13A-7D)") (class "Default")
      (node (ref "IC13") (pin "17") (pinfunction "7D_17") (pintype "input"))
      (node (ref "IN3-4") (pin "5") (pinfunction "5_5") (pintype "passive"))
    )
    (net (code "98") (name "Net-(IC13A-8D)") (class "Default")
      (node (ref "IC13") (pin "18") (pinfunction "8D_18") (pintype "input"))
      (node (ref "IN3-4") (pin "7") (pinfunction "7_7") (pintype "passive"))
    )
    (net (code "99") (name "Net-(IC14A-1D)") (class "Default")
      (node (ref "IC14") (pin "3") (pinfunction "1D_3") (pintype "input"))
      (node (ref "IN3-4") (pin "10") (pinfunction "10_10") (pintype "passive"))
    )
    (net (code "100") (name "Net-(IC14A-2D)") (class "Default")
      (node (ref "IC14") (pin "4") (pinfunction "2D_4") (pintype "input"))
      (node (ref "IN3-4") (pin "12") (pinfunction "12_12") (pintype "passive"))
    )
    (net (code "101") (name "Net-(IC14A-3D)") (class "Default")
      (node (ref "IC14") (pin "7") (pinfunction "3D_7") (pintype "input"))
      (node (ref "IN3-4") (pin "14") (pinfunction "14_14") (pintype "passive"))
    )
    (net (code "102") (name "Net-(IC14A-4D)") (class "Default")
      (node (ref "IC14") (pin "8") (pinfunction "4D_8") (pintype "input"))
      (node (ref "IN3-4") (pin "16") (pinfunction "16_16") (pintype "passive"))
    )
    (net (code "103") (name "Net-(IC14A-5D)") (class "Default")
      (node (ref "IC14") (pin "13") (pinfunction "5D_13") (pintype "input"))
      (node (ref "IN3-4") (pin "9") (pinfunction "9_9") (pintype "passive"))
    )
    (net (code "104") (name "Net-(IC14A-6D)") (class "Default")
      (node (ref "IC14") (pin "14") (pinfunction "6D_14") (pintype "input"))
      (node (ref "IN3-4") (pin "11") (pinfunction "11_11") (pintype "passive"))
    )
    (net (code "105") (name "Net-(IC14A-7D)") (class "Default")
      (node (ref "IC14") (pin "17") (pinfunction "7D_17") (pintype "input"))
      (node (ref "IN3-4") (pin "13") (pinfunction "13_13") (pintype "passive"))
    )
    (net (code "106") (name "Net-(IC14A-8D)") (class "Default")
      (node (ref "IC14") (pin "18") (pinfunction "8D_18") (pintype "input"))
      (node (ref "IN3-4") (pin "15") (pinfunction "15_15") (pintype "passive"))
    )
    (net (code "107") (name "Net-(IC15A-1D)") (class "Default")
      (node (ref "IC15") (pin "3") (pinfunction "1D_3") (pintype "input"))
      (node (ref "IN5-6") (pin "2") (pinfunction "2_2") (pintype "passive"))
    )
    (net (code "108") (name "Net-(IC15A-2D)") (class "Default")
      (node (ref "IC15") (pin "4") (pinfunction "2D_4") (pintype "input"))
      (node (ref "IN5-6") (pin "4") (pinfunction "4_4") (pintype "passive"))
    )
    (net (code "109") (name "Net-(IC15A-3D)") (class "Default")
      (node (ref "IC15") (pin "7") (pinfunction "3D_7") (pintype "input"))
      (node (ref "IN5-6") (pin "6") (pinfunction "6_6") (pintype "passive"))
    )
    (net (code "110") (name "Net-(IC15A-4D)") (class "Default")
      (node (ref "IC15") (pin "8") (pinfunction "4D_8") (pintype "input"))
      (node (ref "IN5-6") (pin "8") (pinfunction "8_8") (pintype "passive"))
    )
    (net (code "111") (name "Net-(IC15A-5D)") (class "Default")
      (node (ref "IC15") (pin "13") (pinfunction "5D_13") (pintype "input"))
      (node (ref "IN5-6") (pin "1") (pinfunction "1_1") (pintype "passive"))
    )
    (net (code "112") (name "Net-(IC15A-6D)") (class "Default")
      (node (ref "IC15") (pin "14") (pinfunction "6D_14") (pintype "input"))
      (node (ref "IN5-6") (pin "3") (pinfunction "3_3") (pintype "passive"))
    )
    (net (code "113") (name "Net-(IC15A-7D)") (class "Default")
      (node (ref "IC15") (pin "17") (pinfunction "7D_17") (pintype "input"))
      (node (ref "IN5-6") (pin "5") (pinfunction "5_5") (pintype "passive"))
    )
    (net (code "114") (name "Net-(IC15A-8D)") (class "Default")
      (node (ref "IC15") (pin "18") (pinfunction "8D_18") (pintype "input"))
      (node (ref "IN5-6") (pin "7") (pinfunction "7_7") (pintype "passive"))
    )
    (net (code "115") (name "Net-(IC16A-1D)") (class "Default")
      (node (ref "IC16") (pin "3") (pinfunction "1D_3") (pintype "input"))
      (node (ref "IN5-6") (pin "10") (pinfunction "10_10") (pintype "passive"))
    )
    (net (code "116") (name "Net-(IC16A-2D)") (class "Default")
      (node (ref "IC16") (pin "4") (pinfunction "2D_4") (pintype "input"))
      (node (ref "IN5-6") (pin "12") (pinfunction "12_12") (pintype "passive"))
    )
    (net (code "117") (name "Net-(IC16A-3D)") (class "Default")
      (node (ref "IC16") (pin "7") (pinfunction "3D_7") (pintype "input"))
      (node (ref "IN5-6") (pin "14") (pinfunction "14_14") (pintype "passive"))
    )
    (net (code "118") (name "Net-(IC16A-4D)") (class "Default")
      (node (ref "IC16") (pin "8") (pinfunction "4D_8") (pintype "input"))
      (node (ref "IN5-6") (pin "16") (pinfunction "16_16") (pintype "passive"))
    )
    (net (code "119") (name "Net-(IC16A-5D)") (class "Default")
      (node (ref "IC16") (pin "13") (pinfunction "5D_13") (pintype "input"))
      (node (ref "IN5-6") (pin "9") (pinfunction "9_9") (pintype "passive"))
    )
    (net (code "120") (name "Net-(IC16A-6D)") (class "Default")
      (node (ref "IC16") (pin "14") (pinfunction "6D_14") (pintype "input"))
      (node (ref "IN5-6") (pin "11") (pinfunction "11_11") (pintype "passive"))
    )
    (net (code "121") (name "Net-(IC16A-7D)") (class "Default")
      (node (ref "IC16") (pin "17") (pinfunction "7D_17") (pintype "input"))
      (node (ref "IN5-6") (pin "13") (pinfunction "13_13") (pintype "passive"))
    )
    (net (code "122") (name "Net-(IC16A-8D)") (class "Default")
      (node (ref "IC16") (pin "18") (pinfunction "8D_18") (pintype "input"))
      (node (ref "IN5-6") (pin "15") (pinfunction "15_15") (pintype "passive"))
    )
    (net (code "123") (name "Net-(IC17A-1D)") (class "Default")
      (node (ref "IC17") (pin "3") (pinfunction "1D_3") (pintype "input"))
      (node (ref "IN7-8") (pin "2") (pinfunction "2_2") (pintype "passive"))
    )
    (net (code "124") (name "Net-(IC17A-2D)") (class "Default")
      (node (ref "IC17") (pin "4") (pinfunction "2D_4") (pintype "input"))
      (node (ref "IN7-8") (pin "4") (pinfunction "4_4") (pintype "passive"))
    )
    (net (code "125") (name "Net-(IC17A-3D)") (class "Default")
      (node (ref "IC17") (pin "7") (pinfunction "3D_7") (pintype "input"))
      (node (ref "IN7-8") (pin "6") (pinfunction "6_6") (pintype "passive"))
    )
    (net (code "126") (name "Net-(IC17A-4D)") (class "Default")
      (node (ref "IC17") (pin "8") (pinfunction "4D_8") (pintype "input"))
      (node (ref "IN7-8") (pin "8") (pinfunction "8_8") (pintype "passive"))
    )
    (net (code "127") (name "Net-(IC17A-5D)") (class "Default")
      (node (ref "IC17") (pin "13") (pinfunction "5D_13") (pintype "input"))
      (node (ref "IN7-8") (pin "1") (pinfunction "1_1") (pintype "passive"))
    )
    (net (code "128") (name "Net-(IC17A-6D)") (class "Default")
      (node (ref "IC17") (pin "14") (pinfunction "6D_14") (pintype "input"))
      (node (ref "IN7-8") (pin "3") (pinfunction "3_3") (pintype "passive"))
    )
    (net (code "129") (name "Net-(IC17A-7D)") (class "Default")
      (node (ref "IC17") (pin "17") (pinfunction "7D_17") (pintype "input"))
      (node (ref "IN7-8") (pin "5") (pinfunction "5_5") (pintype "passive"))
    )
    (net (code "130") (name "Net-(IC17A-8D)") (class "Default")
      (node (ref "IC17") (pin "18") (pinfunction "8D_18") (pintype "input"))
      (node (ref "IN7-8") (pin "7") (pinfunction "7_7") (pintype "passive"))
    )
    (net (code "131") (name "Net-(IC18A-1D)") (class "Default")
      (node (ref "IC18") (pin "3") (pinfunction "1D_3") (pintype "input"))
      (node (ref "IN7-8") (pin "10") (pinfunction "10_10") (pintype "passive"))
    )
    (net (code "132") (name "Net-(IC18A-2D)") (class "Default")
      (node (ref "IC18") (pin "4") (pinfunction "2D_4") (pintype "input"))
      (node (ref "IN7-8") (pin "12") (pinfunction "12_12") (pintype "passive"))
    )
    (net (code "133") (name "Net-(IC18A-3D)") (class "Default")
      (node (ref "IC18") (pin "7") (pinfunction "3D_7") (pintype "input"))
      (node (ref "IN7-8") (pin "14") (pinfunction "14_14") (pintype "passive"))
    )
    (net (code "134") (name "Net-(IC18A-4D)") (class "Default")
      (node (ref "IC18") (pin "8") (pinfunction "4D_8") (pintype "input"))
      (node (ref "IN7-8") (pin "16") (pinfunction "16_16") (pintype "passive"))
    )
    (net (code "135") (name "Net-(IC18A-5D)") (class "Default")
      (node (ref "IC18") (pin "13") (pinfunction "5D_13") (pintype "input"))
      (node (ref "IN7-8") (pin "9") (pinfunction "9_9") (pintype "passive"))
    )
    (net (code "136") (name "Net-(IC18A-6D)") (class "Default")
      (node (ref "IC18") (pin "14") (pinfunction "6D_14") (pintype "input"))
      (node (ref "IN7-8") (pin "11") (pinfunction "11_11") (pintype "passive"))
    )
    (net (code "137") (name "Net-(IC18A-7D)") (class "Default")
      (node (ref "IC18") (pin "17") (pinfunction "7D_17") (pintype "input"))
      (node (ref "IN7-8") (pin "13") (pinfunction "13_13") (pintype "passive"))
    )
    (net (code "138") (name "Net-(IC18A-8D)") (class "Default")
      (node (ref "IC18") (pin "18") (pinfunction "8D_18") (pintype "input"))
      (node (ref "IN7-8") (pin "15") (pinfunction "15_15") (pintype "passive"))
    )
    (net (code "139") (name "Net-(IC19A-Y0)") (class "Default")
      (node (ref "IC19") (pin "15") (pinfunction "Y0_15") (pintype "output"))
      (node (ref "JP1") (pin "1") (pinfunction "1_1") (pintype "passive"))
    )
    (net (code "140") (name "Net-(IC19A-Y1)") (class "Default")
      (node (ref "IC19") (pin "14") (pinfunction "Y1_14") (pintype "output"))
      (node (ref "JP1") (pin "3") (pinfunction "3_3") (pintype "passive"))
    )
    (net (code "141") (name "Net-(IC19A-Y2)") (class "Default")
      (node (ref "IC19") (pin "13") (pinfunction "Y2_13") (pintype "output"))
      (node (ref "JP1") (pin "5") (pinfunction "5_5") (pintype "passive"))
    )
    (net (code "142") (name "Net-(IC19A-Y3)") (class "Default")
      (node (ref "IC19") (pin "12") (pinfunction "Y3_12") (pintype "output"))
      (node (ref "JP1") (pin "7") (pinfunction "7_7") (pintype "passive"))
    )
    (net (code "143") (name "Net-(IC19A-Y4)") (class "Default")
      (node (ref "IC19") (pin "11") (pinfunction "Y4_11") (pintype "output"))
      (node (ref "JP1") (pin "9") (pinfunction "9_9") (pintype "passive"))
    )
    (net (code "144") (name "Net-(IC19A-Y5)") (class "Default")
      (node (ref "IC19") (pin "10") (pinfunction "Y5_10") (pintype "output"))
      (node (ref "JP1") (pin "11") (pinfunction "11_11") (pintype "passive"))
    )
    (net (code "145") (name "Net-(IC19A-Y6)") (class "Default")
      (node (ref "IC19") (pin "9") (pinfunction "Y6_9") (pintype "output"))
      (node (ref "JP1") (pin "13") (pinfunction "13_13") (pintype "passive"))
    )
    (net (code "146") (name "Net-(IC19A-Y7)") (class "Default")
      (node (ref "IC19") (pin "7") (pinfunction "Y7_7") (pintype "output"))
      (node (ref "JP1") (pin "15") (pinfunction "15_15") (pintype "passive"))
    )
    (net (code "147") (name "OUT00") (class "Default")
      (node (ref "IC1") (pin "11") (pinfunction "CLK_11") (pintype "input"))
      (node (ref "IC10") (pin "15") (pinfunction "Y0_15") (pintype "output"))
    )
    (net (code "148") (name "OUT01") (class "Default")
      (node (ref "IC10") (pin "14") (pinfunction "Y1_14") (pintype "output"))
      (node (ref "IC2") (pin "11") (pinfunction "CLK_11") (pintype "input"))
    )
    (net (code "149") (name "OUT02") (class "Default")
      (node (ref "IC10") (pin "13") (pinfunction "Y2_13") (pintype "output"))
      (node (ref "IC3") (pin "11") (pinfunction "CLK_11") (pintype "input"))
    )
    (net (code "150") (name "OUT03") (class "Default")
      (node (ref "IC10") (pin "12") (pinfunction "Y3_12") (pintype "output"))
      (node (ref "IC4") (pin "11") (pinfunction "CLK_11") (pintype "input"))
    )
    (net (code "151") (name "OUT04") (class "Default")
      (node (ref "IC10") (pin "11") (pinfunction "Y4_11") (pintype "output"))
      (node (ref "IC5") (pin "11") (pinfunction "CLK_11") (pintype "input"))
    )
    (net (code "152") (name "OUT05") (class "Default")
      (node (ref "IC10") (pin "10") (pinfunction "Y5_10") (pintype "output"))
      (node (ref "IC6") (pin "11") (pinfunction "CLK_11") (pintype "input"))
    )
    (net (code "153") (name "OUT06") (class "Default")
      (node (ref "IC10") (pin "9") (pinfunction "Y6_9") (pintype "output"))
      (node (ref "IC7") (pin "11") (pinfunction "CLK_11") (pintype "input"))
    )
    (net (code "154") (name "OUT07") (class "Default")
      (node (ref "IC10") (pin "7") (pinfunction "Y7_7") (pintype "output"))
      (node (ref "IC8") (pin "11") (pinfunction "CLK_11") (pintype "input"))
    )
    (net (code "155") (name "PIA-A0") (class "Default")
      (node (ref "CORE-IO") (pin "1") (pinfunction "1_1") (pintype "passive"))
      (node (ref "IC1") (pin "3") (pinfunction "1D_3") (pintype "input"))
      (node (ref "IC11") (pin "2") (pinfunction "1Q_2") (pintype "tri_state"))
      (node (ref "IC12") (pin "2") (pinfunction "1Q_2") (pintype "tri_state"))
      (node (ref "IC13") (pin "2") (pinfunction "1Q_2") (pintype "tri_state"))
      (node (ref "IC14") (pin "2") (pinfunction "1Q_2") (pintype "tri_state"))
      (node (ref "IC15") (pin "2") (pinfunction "1Q_2") (pintype "tri_state"))
      (node (ref "IC16") (pin "2") (pinfunction "1Q_2") (pintype "tri_state"))
      (node (ref "IC17") (pin "2") (pinfunction "1Q_2") (pintype "tri_state"))
      (node (ref "IC18") (pin "2") (pinfunction "1Q_2") (pintype "tri_state"))
      (node (ref "IC2") (pin "3") (pinfunction "1D_3") (pintype "input"))
      (node (ref "IC3") (pin "3") (pinfunction "1D_3") (pintype "input"))
      (node (ref "IC4") (pin "3") (pinfunction "1D_3") (pintype "input"))
      (node (ref "IC5") (pin "3") (pinfunction "1D_3") (pintype "input"))
      (node (ref "IC6") (pin "3") (pinfunction "1D_3") (pintype "input"))
      (node (ref "IC7") (pin "3") (pinfunction "1D_3") (pintype "input"))
      (node (ref "IC8") (pin "3") (pinfunction "1D_3") (pintype "input"))
    )
    (net (code "156") (name "PIA-A1") (class "Default")
      (node (ref "CORE-IO") (pin "2") (pinfunction "2_2") (pintype "passive"))
      (node (ref "IC1") (pin "4") (pinfunction "2D_4") (pintype "input"))
      (node (ref "IC11") (pin "5") (pinfunction "2Q_5") (pintype "tri_state"))
      (node (ref "IC12") (pin "5") (pinfunction "2Q_5") (pintype "tri_state"))
      (node (ref "IC13") (pin "5") (pinfunction "2Q_5") (pintype "tri_state"))
      (node (ref "IC14") (pin "5") (pinfunction "2Q_5") (pintype "tri_state"))
      (node (ref "IC15") (pin "5") (pinfunction "2Q_5") (pintype "tri_state"))
      (node (ref "IC16") (pin "5") (pinfunction "2Q_5") (pintype "tri_state"))
      (node (ref "IC17") (pin "5") (pinfunction "2Q_5") (pintype "tri_state"))
      (node (ref "IC18") (pin "5") (pinfunction "2Q_5") (pintype "tri_state"))
      (node (ref "IC2") (pin "4") (pinfunction "2D_4") (pintype "input"))
      (node (ref "IC3") (pin "4") (pinfunction "2D_4") (pintype "input"))
      (node (ref "IC4") (pin "4") (pinfunction "2D_4") (pintype "input"))
      (node (ref "IC5") (pin "4") (pinfunction "2D_4") (pintype "input"))
      (node (ref "IC6") (pin "4") (pinfunction "2D_4") (pintype "input"))
      (node (ref "IC7") (pin "4") (pinfunction "2D_4") (pintype "input"))
      (node (ref "IC8") (pin "4") (pinfunction "2D_4") (pintype "input"))
    )
    (net (code "157") (name "PIA-A2") (class "Default")
      (node (ref "CORE-IO") (pin "3") (pinfunction "3_3") (pintype "passive"))
      (node (ref "IC1") (pin "7") (pinfunction "3D_7") (pintype "input"))
      (node (ref "IC11") (pin "6") (pinfunction "3Q_6") (pintype "tri_state"))
      (node (ref "IC12") (pin "6") (pinfunction "3Q_6") (pintype "tri_state"))
      (node (ref "IC13") (pin "6") (pinfunction "3Q_6") (pintype "tri_state"))
      (node (ref "IC14") (pin "6") (pinfunction "3Q_6") (pintype "tri_state"))
      (node (ref "IC15") (pin "6") (pinfunction "3Q_6") (pintype "tri_state"))
      (node (ref "IC16") (pin "6") (pinfunction "3Q_6") (pintype "tri_state"))
      (node (ref "IC17") (pin "6") (pinfunction "3Q_6") (pintype "tri_state"))
      (node (ref "IC18") (pin "6") (pinfunction "3Q_6") (pintype "tri_state"))
      (node (ref "IC2") (pin "7") (pinfunction "3D_7") (pintype "input"))
      (node (ref "IC3") (pin "7") (pinfunction "3D_7") (pintype "input"))
      (node (ref "IC4") (pin "7") (pinfunction "3D_7") (pintype "input"))
      (node (ref "IC5") (pin "7") (pinfunction "3D_7") (pintype "input"))
      (node (ref "IC6") (pin "7") (pinfunction "3D_7") (pintype "input"))
      (node (ref "IC7") (pin "7") (pinfunction "3D_7") (pintype "input"))
      (node (ref "IC8") (pin "7") (pinfunction "3D_7") (pintype "input"))
    )
    (net (code "158") (name "PIA-A3") (class "Default")
      (node (ref "CORE-IO") (pin "4") (pinfunction "4_4") (pintype "passive"))
      (node (ref "IC1") (pin "8") (pinfunction "4D_8") (pintype "input"))
      (node (ref "IC11") (pin "9") (pinfunction "4Q_9") (pintype "tri_state"))
      (node (ref "IC12") (pin "9") (pinfunction "4Q_9") (pintype "tri_state"))
      (node (ref "IC13") (pin "9") (pinfunction "4Q_9") (pintype "tri_state"))
      (node (ref "IC14") (pin "9") (pinfunction "4Q_9") (pintype "tri_state"))
      (node (ref "IC15") (pin "9") (pinfunction "4Q_9") (pintype "tri_state"))
      (node (ref "IC16") (pin "9") (pinfunction "4Q_9") (pintype "tri_state"))
      (node (ref "IC17") (pin "9") (pinfunction "4Q_9") (pintype "tri_state"))
      (node (ref "IC18") (pin "9") (pinfunction "4Q_9") (pintype "tri_state"))
      (node (ref "IC2") (pin "8") (pinfunction "4D_8") (pintype "input"))
      (node (ref "IC3") (pin "8") (pinfunction "4D_8") (pintype "input"))
      (node (ref "IC4") (pin "8") (pinfunction "4D_8") (pintype "input"))
      (node (ref "IC5") (pin "8") (pinfunction "4D_8") (pintype "input"))
      (node (ref "IC6") (pin "8") (pinfunction "4D_8") (pintype "input"))
      (node (ref "IC7") (pin "8") (pinfunction "4D_8") (pintype "input"))
      (node (ref "IC8") (pin "8") (pinfunction "4D_8") (pintype "input"))
    )
    (net (code "159") (name "PIA-A4") (class "Default")
      (node (ref "CORE-IO") (pin "5") (pinfunction "5_5") (pintype "passive"))
      (node (ref "IC1") (pin "13") (pinfunction "5D_13") (pintype "input"))
      (node (ref "IC11") (pin "12") (pinfunction "5Q_12") (pintype "tri_state"))
      (node (ref "IC12") (pin "12") (pinfunction "5Q_12") (pintype "tri_state"))
      (node (ref "IC13") (pin "12") (pinfunction "5Q_12") (pintype "tri_state"))
      (node (ref "IC14") (pin "12") (pinfunction "5Q_12") (pintype "tri_state"))
      (node (ref "IC15") (pin "12") (pinfunction "5Q_12") (pintype "tri_state"))
      (node (ref "IC16") (pin "12") (pinfunction "5Q_12") (pintype "tri_state"))
      (node (ref "IC17") (pin "12") (pinfunction "5Q_12") (pintype "tri_state"))
      (node (ref "IC18") (pin "12") (pinfunction "5Q_12") (pintype "tri_state"))
      (node (ref "IC2") (pin "13") (pinfunction "5D_13") (pintype "input"))
      (node (ref "IC3") (pin "13") (pinfunction "5D_13") (pintype "input"))
      (node (ref "IC4") (pin "13") (pinfunction "5D_13") (pintype "input"))
      (node (ref "IC5") (pin "13") (pinfunction "5D_13") (pintype "input"))
      (node (ref "IC6") (pin "13") (pinfunction "5D_13") (pintype "input"))
      (node (ref "IC7") (pin "13") (pinfunction "5D_13") (pintype "input"))
      (node (ref "IC8") (pin "13") (pinfunction "5D_13") (pintype "input"))
    )
    (net (code "160") (name "PIA-A5") (class "Default")
      (node (ref "CORE-IO") (pin "6") (pinfunction "6_6") (pintype "passive"))
      (node (ref "IC1") (pin "14") (pinfunction "6D_14") (pintype "input"))
      (node (ref "IC11") (pin "15") (pinfunction "6Q_15") (pintype "tri_state"))
      (node (ref "IC12") (pin "15") (pinfunction "6Q_15") (pintype "tri_state"))
      (node (ref "IC13") (pin "15") (pinfunction "6Q_15") (pintype "tri_state"))
      (node (ref "IC14") (pin "15") (pinfunction "6Q_15") (pintype "tri_state"))
      (node (ref "IC15") (pin "15") (pinfunction "6Q_15") (pintype "tri_state"))
      (node (ref "IC16") (pin "15") (pinfunction "6Q_15") (pintype "tri_state"))
      (node (ref "IC17") (pin "15") (pinfunction "6Q_15") (pintype "tri_state"))
      (node (ref "IC18") (pin "15") (pinfunction "6Q_15") (pintype "tri_state"))
      (node (ref "IC2") (pin "14") (pinfunction "6D_14") (pintype "input"))
      (node (ref "IC3") (pin "14") (pinfunction "6D_14") (pintype "input"))
      (node (ref "IC4") (pin "14") (pinfunction "6D_14") (pintype "input"))
      (node (ref "IC5") (pin "14") (pinfunction "6D_14") (pintype "input"))
      (node (ref "IC6") (pin "14") (pinfunction "6D_14") (pintype "input"))
      (node (ref "IC7") (pin "14") (pinfunction "6D_14") (pintype "input"))
      (node (ref "IC8") (pin "14") (pinfunction "6D_14") (pintype "input"))
    )
    (net (code "161") (name "PIA-A6") (class "Default")
      (node (ref "CORE-IO") (pin "7") (pinfunction "7_7") (pintype "passive"))
      (node (ref "IC1") (pin "17") (pinfunction "7D_17") (pintype "input"))
      (node (ref "IC11") (pin "16") (pinfunction "7Q_16") (pintype "tri_state"))
      (node (ref "IC12") (pin "16") (pinfunction "7Q_16") (pintype "tri_state"))
      (node (ref "IC13") (pin "16") (pinfunction "7Q_16") (pintype "tri_state"))
      (node (ref "IC14") (pin "16") (pinfunction "7Q_16") (pintype "tri_state"))
      (node (ref "IC15") (pin "16") (pinfunction "7Q_16") (pintype "tri_state"))
      (node (ref "IC16") (pin "16") (pinfunction "7Q_16") (pintype "tri_state"))
      (node (ref "IC17") (pin "16") (pinfunction "7Q_16") (pintype "tri_state"))
      (node (ref "IC18") (pin "16") (pinfunction "7Q_16") (pintype "tri_state"))
      (node (ref "IC2") (pin "17") (pinfunction "7D_17") (pintype "input"))
      (node (ref "IC3") (pin "17") (pinfunction "7D_17") (pintype "input"))
      (node (ref "IC4") (pin "17") (pinfunction "7D_17") (pintype "input"))
      (node (ref "IC5") (pin "17") (pinfunction "7D_17") (pintype "input"))
      (node (ref "IC6") (pin "17") (pinfunction "7D_17") (pintype "input"))
      (node (ref "IC7") (pin "17") (pinfunction "7D_17") (pintype "input"))
      (node (ref "IC8") (pin "17") (pinfunction "7D_17") (pintype "input"))
    )
    (net (code "162") (name "PIA-A7") (class "Default")
      (node (ref "CORE-IO") (pin "8") (pinfunction "8_8") (pintype "passive"))
      (node (ref "IC1") (pin "18") (pinfunction "8D_18") (pintype "input"))
      (node (ref "IC11") (pin "19") (pinfunction "8Q_19") (pintype "tri_state"))
      (node (ref "IC12") (pin "19") (pinfunction "8Q_19") (pintype "tri_state"))
      (node (ref "IC13") (pin "19") (pinfunction "8Q_19") (pintype "tri_state"))
      (node (ref "IC14") (pin "19") (pinfunction "8Q_19") (pintype "tri_state"))
      (node (ref "IC15") (pin "19") (pinfunction "8Q_19") (pintype "tri_state"))
      (node (ref "IC16") (pin "19") (pinfunction "8Q_19") (pintype "tri_state"))
      (node (ref "IC17") (pin "19") (pinfunction "8Q_19") (pintype "tri_state"))
      (node (ref "IC18") (pin "19") (pinfunction "8Q_19") (pintype "tri_state"))
      (node (ref "IC2") (pin "18") (pinfunction "8D_18") (pintype "input"))
      (node (ref "IC3") (pin "18") (pinfunction "8D_18") (pintype "input"))
      (node (ref "IC4") (pin "18") (pinfunction "8D_18") (pintype "input"))
      (node (ref "IC5") (pin "18") (pinfunction "8D_18") (pintype "input"))
      (node (ref "IC6") (pin "18") (pinfunction "8D_18") (pintype "input"))
      (node (ref "IC7") (pin "18") (pinfunction "8D_18") (pintype "input"))
      (node (ref "IC8") (pin "18") (pinfunction "8D_18") (pintype "input"))
    )
    (net (code "163") (name "PIA-B0") (class "Default")
      (node (ref "CORE-IO") (pin "13") (pinfunction "13_13") (pintype "passive"))
      (node (ref "IC10") (pin "1") (pinfunction "A_1") (pintype "input"))
      (node (ref "IC9") (pin "1") (pinfunction "A_1") (pintype "input"))
    )
    (net (code "164") (name "PIA-B1") (class "Default")
      (node (ref "CORE-IO") (pin "14") (pinfunction "14_14") (pintype "passive"))
      (node (ref "IC10") (pin "2") (pinfunction "B_2") (pintype "input"))
      (node (ref "IC9") (pin "2") (pinfunction "B_2") (pintype "input"))
    )
    (net (code "165") (name "PIA-B2") (class "Default")
      (node (ref "CORE-IO") (pin "15") (pinfunction "15_15") (pintype "passive"))
      (node (ref "IC10") (pin "3") (pinfunction "C_3") (pintype "input"))
      (node (ref "IC9") (pin "3") (pinfunction "C_3") (pintype "input"))
    )
    (net (code "166") (name "PIA-B3") (class "Default")
      (node (ref "CORE-IO") (pin "16") (pinfunction "16_16") (pintype "passive"))
      (node (ref "IC19") (pin "1") (pinfunction "A_1") (pintype "input"))
    )
    (net (code "167") (name "PIA-B4") (class "Default")
      (node (ref "CORE-IO") (pin "17") (pinfunction "17_17") (pintype "passive"))
      (node (ref "IC19") (pin "2") (pinfunction "B_2") (pintype "input"))
    )
    (net (code "168") (name "PIA-B5") (class "Default")
      (node (ref "CORE-IO") (pin "18") (pinfunction "18_18") (pintype "passive"))
      (node (ref "IC19") (pin "3") (pinfunction "C_3") (pintype "input"))
    )
    (net (code "169") (name "PIA-B6") (class "Default")
      (node (ref "CORE-IO") (pin "19") (pinfunction "19_19") (pintype "passive"))
      (node (ref "IC10") (pin "6") (pinfunction "G1_6") (pintype "input"))
      (node (ref "IC9") (pin "4") (pinfunction "G2A_4") (pintype "input"))
    )
    (net (code "170") (name "PIA-B7") (class "Default")
      (node (ref "CORE-IO") (pin "20") (pinfunction "20_20") (pintype "passive"))
      (node (ref "IC19") (pin "5") (pinfunction "G2B_5") (pintype "input"))
      (node (ref "JP1") (pin "17") (pinfunction "17_17") (pintype "passive"))
    )
    (net (code "171") (name "VCC") (class "Default")
      (node (ref "BYP1") (pin "1") (pinfunction "1_1") (pintype "passive"))
      (node (ref "BYP10") (pin "1") (pinfunction "1_1") (pintype "passive"))
      (node (ref "BYP11") (pin "1") (pinfunction "1_1") (pintype "passive"))
      (node (ref "BYP12") (pin "1") (pinfunction "1_1") (pintype "passive"))
      (node (ref "BYP13") (pin "1") (pinfunction "1_1") (pintype "passive"))
      (node (ref "BYP14") (pin "1") (pinfunction "1_1") (pintype "passive"))
      (node (ref "BYP15") (pin "1") (pinfunction "1_1") (pintype "passive"))
      (node (ref "BYP16") (pin "1") (pinfunction "1_1") (pintype "passive"))
      (node (ref "BYP17") (pin "1") (pinfunction "1_1") (pintype "passive"))
      (node (ref "BYP18") (pin "1") (pinfunction "1_1") (pintype "passive"))
      (node (ref "BYP19") (pin "1") (pinfunction "1_1") (pintype "passive"))
      (node (ref "BYP2") (pin "1") (pinfunction "1_1") (pintype "passive"))
      (node (ref "BYP20") (pin "1") (pinfunction "1_1") (pintype "passive"))
      (node (ref "BYP3") (pin "1") (pinfunction "1_1") (pintype "passive"))
      (node (ref "BYP4") (pin "1") (pinfunction "1_1") (pintype "passive"))
      (node (ref "BYP5") (pin "1") (pinfunction "1_1") (pintype "passive"))
      (node (ref "BYP6") (pin "1") (pinfunction "1_1") (pintype "passive"))
      (node (ref "BYP7") (pin "1") (pinfunction "1_1") (pintype "passive"))
      (node (ref "BYP8") (pin "1") (pinfunction "1_1") (pintype "passive"))
      (node (ref "BYP9") (pin "1") (pinfunction "1_1") (pintype "passive"))
      (node (ref "CORE-IO") (pin "12") (pinfunction "12_12") (pintype "passive"))
      (node (ref "CORE-IO") (pin "9") (pinfunction "9_9") (pintype "passive"))
      (node (ref "IC11") (pin "11") (pinfunction "ENC_11") (pintype "input"))
      (node (ref "IC12") (pin "11") (pinfunction "ENC_11") (pintype "input"))
      (node (ref "IC13") (pin "11") (pinfunction "ENC_11") (pintype "input"))
      (node (ref "IC14") (pin "11") (pinfunction "ENC_11") (pintype "input"))
      (node (ref "IC15") (pin "11") (pinfunction "ENC_11") (pintype "input"))
      (node (ref "IC16") (pin "11") (pinfunction "ENC_11") (pintype "input"))
      (node (ref "IC17") (pin "11") (pinfunction "ENC_11") (pintype "input"))
      (node (ref "IC18") (pin "11") (pinfunction "ENC_11") (pintype "input"))
      (node (ref "IC19") (pin "6") (pinfunction "G1_6") (pintype "input"))
      (node (ref "IC9") (pin "6") (pinfunction "G1_6") (pintype "input"))
      (node (ref "JP2") (pin "2") (pinfunction "2_2") (pintype "passive"))
    )
  )
)
